# Sheet1.net
KiCad netlist of a schematic drawn in Altium Designer
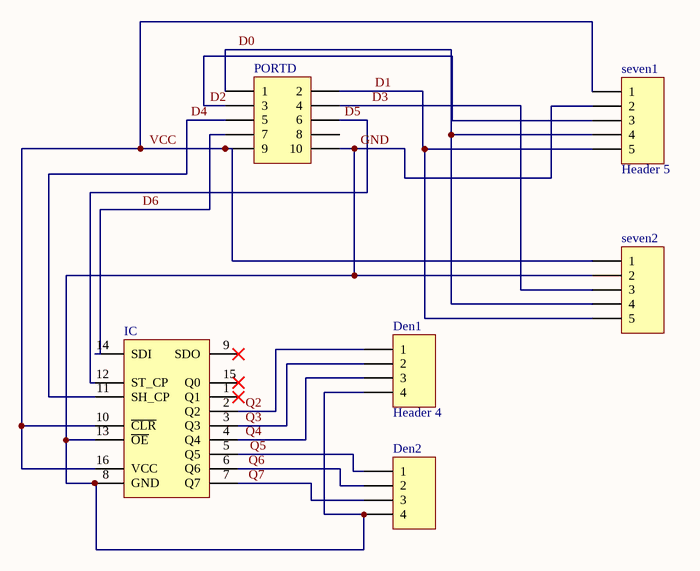
[diagram p0: Sheet1.SchDoc]

(export (version "E")
  (design (tool "Eeschema 10.0.6"))
  (components
    (comp (ref "Den1")
      (value "Header 4")
      (footprint "HDR1X4")
      (description "Header, 4-Pin")
      (fields (field (name "PUBLISHER") "Altium Limited"))
      (libsource (lib "Miscellaneous Connectors") (part "Header 4"))
    )
    (comp (ref "Den2")
      (value "Header 4")
      (footprint "HDR1X4")
      (description "Header, 4-Pin")
      (fields (field (name "PUBLISHER") "Altium Limited"))
      (libsource (lib "Miscellaneous Connectors") (part "Header 4"))
    )
    (comp (ref "IC")
      (value "74HC595")
      (footprint "DIP 16")
      (description "8-bit serial-in, serial or parallel-out  shift register with output latches;  3-state")
      (libsource (lib "BKIT4U_LIB") (part "74HC595"))
    )
    (comp (ref "PORTD")
      (value "Header 5X2")
      (footprint "HDR2X5")
      (description "Header, 5-Pin, Dual row")
      (fields (field (name "PUBLISHER") "Altium Limited"))
      (libsource (lib "My library altium") (part "Header 5X2"))
    )
    (comp (ref "seven1")
      (value "Header 5")
      (footprint "HDR1X5")
      (description "Header, 5-Pin")
      (fields (field (name "PUBLISHER") "Altium Limited"))
      (libsource (lib "Miscellaneous Connectors") (part "Header 5"))
    )
    (comp (ref "seven2")
      (value "Header 5")
      (footprint "HDR1X5")
      (description "Header, 5-Pin")
      (fields (field (name "PUBLISHER") "Altium Limited"))
      (libsource (lib "Miscellaneous Connectors") (part "Header 5"))
    )
  )
  (nets
    (net (code "1") (name "/D0") (class "Default")
      (node (ref "PORTD") (pin "1") (pinfunction "1_1") (pintype "passive"))
      (node (ref "seven1") (pin "4") (pinfunction "4_4") (pintype "passive"))
      (node (ref "seven2") (pin "4") (pinfunction "4_4") (pintype "passive"))
    )
    (net (code "2") (name "/D1") (class "Default")
      (node (ref "PORTD") (pin "2") (pinfunction "2_2") (pintype "passive"))
      (node (ref "seven1") (pin "5") (pinfunction "5_5") (pintype "passive"))
      (node (ref "seven2") (pin "5") (pinfunction "5_5") (pintype "passive"))
    )
    (net (code "3") (name "/D2") (class "Default")
      (node (ref "PORTD") (pin "3") (pinfunction "3_3") (pintype "passive"))
      (node (ref "seven1") (pin "3") (pinfunction "3_3") (pintype "passive"))
    )
    (net (code "4") (name "/D3") (class "Default")
      (node (ref "PORTD") (pin "4") (pinfunction "4_4") (pintype "passive"))
      (node (ref "seven2") (pin "3") (pinfunction "3_3") (pintype "passive"))
    )
    (net (code "5") (name "/D4") (class "Default")
      (node (ref "IC") (pin "11") (pinfunction "SH_CP_11") (pintype "passive"))
      (node (ref "PORTD") (pin "5") (pinfunction "5_5") (pintype "passive"))
    )
    (net (code "6") (name "/D5") (class "Default")
      (node (ref "IC") (pin "12") (pinfunction "ST_CP_12") (pintype "passive"))
      (node (ref "PORTD") (pin "6") (pinfunction "6_6") (pintype "passive"))
    )
    (net (code "7") (name "/D6") (class "Default")
      (node (ref "IC") (pin "14") (pinfunction "SDI_14") (pintype "passive"))
      (node (ref "PORTD") (pin "7") (pinfunction "7_7") (pintype "passive"))
    )
    (net (code "8") (name "/GND") (class "Default")
      (node (ref "Den1") (pin "4") (pinfunction "4_4") (pintype "passive"))
      (node (ref "Den2") (pin "4") (pinfunction "4_4") (pintype "passive"))
      (node (ref "IC") (pin "13") (pinfunction "~{OE}_13") (pintype "passive"))
      (node (ref "IC") (pin "8") (pinfunction "GND_8") (pintype "passive"))
      (node (ref "PORTD") (pin "10") (pinfunction "10_10") (pintype "passive"))
      (node (ref "seven1") (pin "2") (pinfunction "2_2") (pintype "passive"))
      (node (ref "seven2") (pin "2") (pinfunction "2_2") (pintype "passive"))
    )
    (net (code "9") (name "/Q2") (class "Default")
      (node (ref "Den1") (pin "1") (pinfunction "1_1") (pintype "passive"))
      (node (ref "IC") (pin "2") (pinfunction "Q2_2") (pintype "passive"))
    )
    (net (code "10") (name "/Q3") (class "Default")
      (node (ref "Den1") (pin "2") (pinfunction "2_2") (pintype "passive"))
      (node (ref "IC") (pin "3") (pinfunction "Q3_3") (pintype "passive"))
    )
    (net (code "11") (name "/Q4") (class "Default")
      (node (ref "Den1") (pin "3") (pinfunction "3_3") (pintype "passive"))
      (node (ref "IC") (pin "4") (pinfunction "Q4_4") (pintype "passive"))
    )
    (net (code "12") (name "/Q5") (class "Default")
      (node (ref "Den2") (pin "1") (pinfunction "1_1") (pintype "passive"))
      (node (ref "IC") (pin "5") (pinfunction "Q5_5") (pintype "passive"))
    )
    (net (code "13") (name "/Q6") (class "Default")
      (node (ref "Den2") (pin "2") (pinfunction "2_2") (pintype "passive"))
      (node (ref "IC") (pin "6") (pinfunction "Q6_6") (pintype "passive"))
    )
    (net (code "14") (name "/Q7") (class "Default")
      (node (ref "Den2") (pin "3") (pinfunction "3_3") (pintype "passive"))
      (node (ref "IC") (pin "7") (pinfunction "Q7_7") (pintype "passive"))
    )
    (net (code "15") (name "/VCC") (class "Default")
      (node (ref "IC") (pin "10") (pinfunction "~{CLR}_10") (pintype "passive"))
      (node (ref "IC") (pin "16") (pinfunction "VCC_16") (pintype "passive"))
      (node (ref "PORTD") (pin "9") (pinfunction "9_9") (pintype "passive"))
      (node (ref "seven1") (pin "1") (pinfunction "1_1") (pintype "passive"))
      (node (ref "seven2") (pin "1") (pinfunction "1_1") (pintype "passive"))
    )
    (net (code "16") (name "unconnected-(IC-Q0-Pad15)") (class "Default")
      (node (ref "IC") (pin "15") (pinfunction "Q0_15") (pintype "passive+no_connect"))
    )
    (net (code "17") (name "unconnected-(IC-Q1-Pad1)") (class "Default")
      (node (ref "IC") (pin "1") (pinfunction "Q1_1") (pintype "passive+no_connect"))
    )
    (net (code "18") (name "unconnected-(IC-SDO-Pad9)") (class "Default")
      (node (ref "IC") (pin "9") (pinfunction "SDO_9") (pintype "passive+no_connect"))
    )
    (net (code "19") (name "unconnected-(PORTD-Pad8)") (class "Default")
      (node (ref "PORTD") (pin "8") (pinfunction "8_8") (pintype "passive"))
    )
  )
)
